# SCH_hackfest_2025-04-05_final.net
KiCad netlist of a schematic drawn in EasyEDA
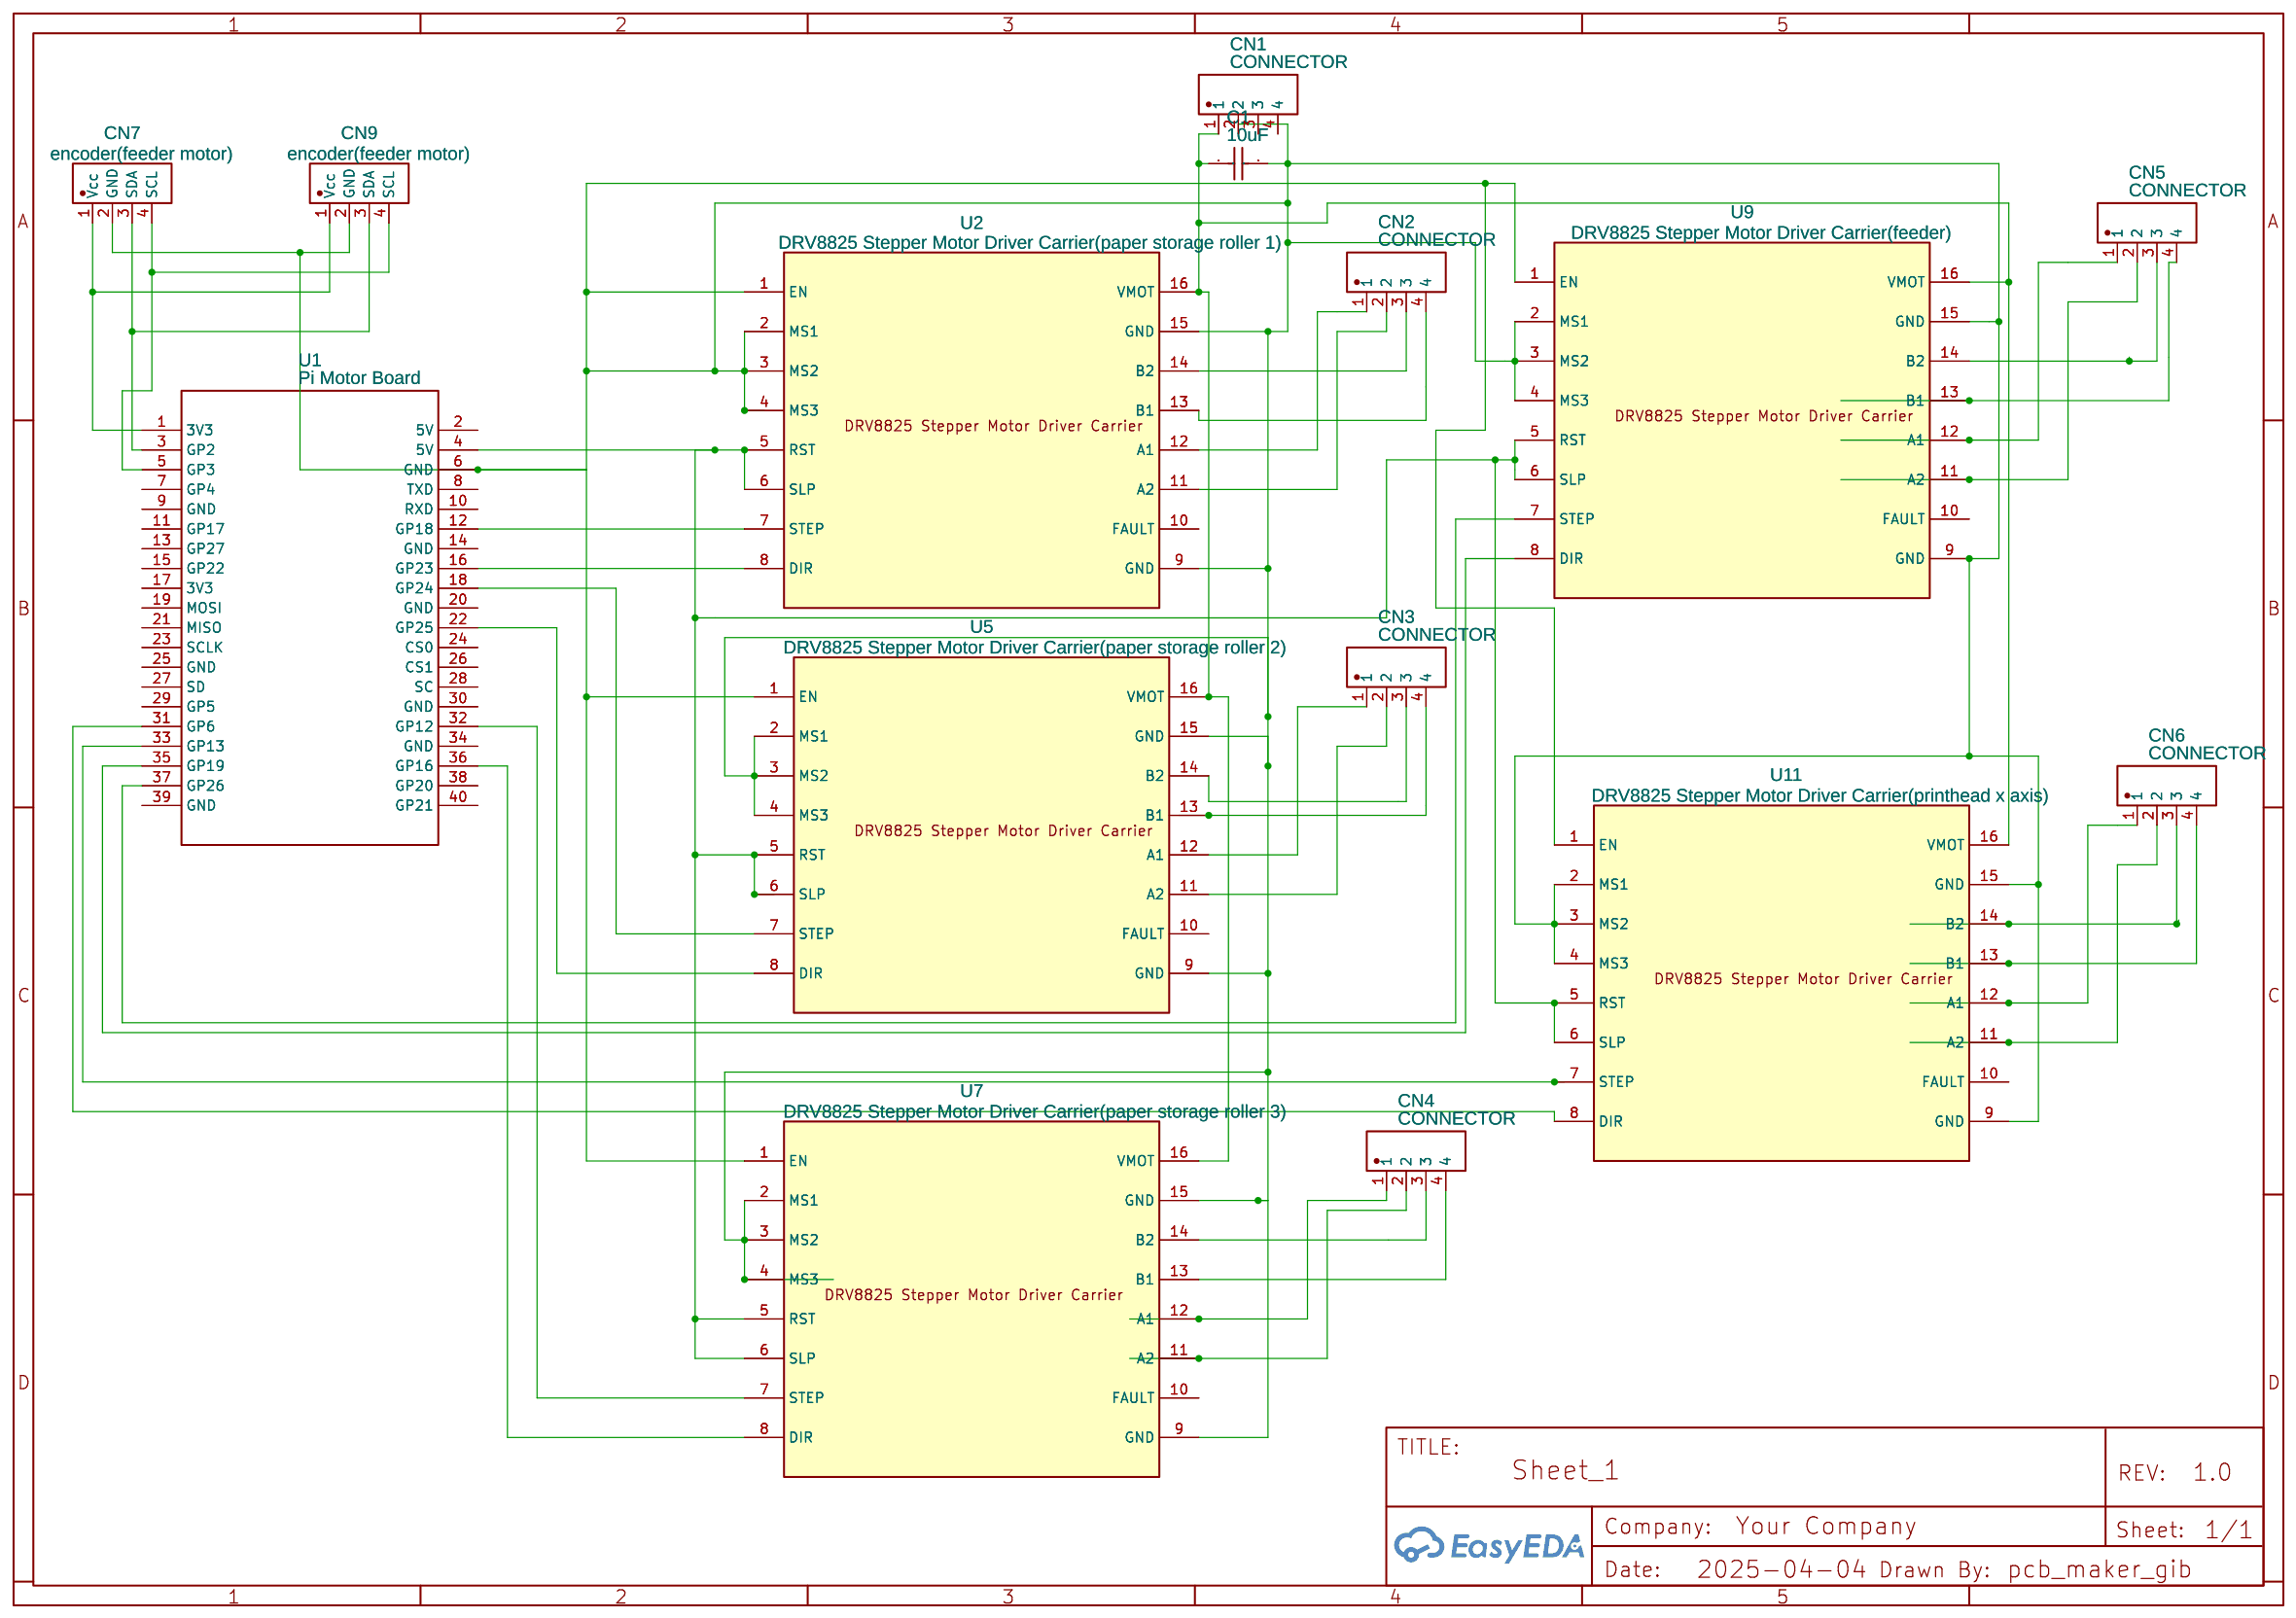
[diagram p0: schematic sheet]

(export (version "E")
  (design (tool "Eeschema 10.0.6"))
  (components
    (comp (ref "C1")
      (value "10uF")
      (fields (field (name "Manufacturer Part") "电容15nf100v"))
      (libsource (lib "") (part "CAPACITOR15NF100V"))
    )
    (comp (ref "CN1") (value "CONNECTOR") (libsource (lib "") (part "CONNECTOR_1")))
    (comp (ref "CN2") (value "CONNECTOR") (libsource (lib "") (part "CONNECTOR_1")))
    (comp (ref "CN3") (value "CONNECTOR") (libsource (lib "") (part "CONNECTOR_1")))
    (comp (ref "CN4") (value "CONNECTOR") (libsource (lib "") (part "CONNECTOR_1")))
    (comp (ref "CN5") (value "CONNECTOR") (libsource (lib "") (part "CONNECTOR_1")))
    (comp (ref "CN6") (value "CONNECTOR") (libsource (lib "") (part "CONNECTOR_1")))
    (comp (ref "CN7")
      (value "encoder(feeder motor)")
      (fields (field (name "Manufacturer Part") "CONNECTOR"))
      (libsource (lib "") (part "CONNECTOR"))
    )
    (comp (ref "CN9")
      (value "encoder(feeder motor)")
      (fields (field (name "Manufacturer Part") "CONNECTOR"))
      (libsource (lib "") (part "CONNECTOR"))
    )
    (comp (ref "U1") (value "Pi Motor Board") (libsource (lib "") (part "Pi Motor Board")))
    (comp (ref "U2")
      (value "DRV8825 Stepper Motor Driver Carrier(paper storage roller 1)")
      (libsource (lib "") (part "DRV8825 Stepper Motor Driver Carrier"))
    )
    (comp (ref "U5")
      (value "DRV8825 Stepper Motor Driver Carrier(paper storage roller 2)")
      (libsource (lib "") (part "DRV8825 Stepper Motor Driver Carrier"))
    )
    (comp (ref "U7")
      (value "DRV8825 Stepper Motor Driver Carrier(paper storage roller 3)")
      (libsource (lib "") (part "DRV8825 Stepper Motor Driver Carrier_1"))
    )
    (comp (ref "U9")
      (value "DRV8825 Stepper Motor Driver Carrier(feeder)")
      (libsource (lib "") (part "DRV8825 Stepper Motor Driver Carrier"))
    )
    (comp (ref "U11")
      (value "DRV8825 Stepper Motor Driver Carrier(printhead x axis)")
      (libsource (lib "") (part "DRV8825 Stepper Motor Driver Carrier"))
    )
  )
  (nets
    (net (code "1") (name "Net-(CN7-GND)") (class "Default")
      (node (ref "C1") (pin "2") (pinfunction "2_2") (pintype "input"))
      (node (ref "CN1") (pin "2") (pinfunction "2_2") (pintype "unspecified"))
      (node (ref "CN7") (pin "2") (pinfunction "GND_2") (pintype "unspecified"))
      (node (ref "CN9") (pin "2") (pinfunction "GND_2") (pintype "unspecified"))
      (node (ref "U1") (pin "6") (pinfunction "GND_6") (pintype "unspecified"))
      (node (ref "U11") (pin "1") (pinfunction "EN_1") (pintype "unspecified"))
      (node (ref "U11") (pin "15") (pinfunction "GND_15") (pintype "unspecified"))
      (node (ref "U11") (pin "2") (pinfunction "MS1_2") (pintype "unspecified"))
      (node (ref "U11") (pin "3") (pinfunction "MS2_3") (pintype "unspecified"))
      (node (ref "U11") (pin "4") (pinfunction "MS3_4") (pintype "unspecified"))
      (node (ref "U11") (pin "9") (pinfunction "GND_9") (pintype "unspecified"))
      (node (ref "U2") (pin "1") (pinfunction "EN_1") (pintype "unspecified"))
      (node (ref "U2") (pin "15") (pinfunction "GND_15") (pintype "unspecified"))
      (node (ref "U2") (pin "2") (pinfunction "MS1_2") (pintype "unspecified"))
      (node (ref "U2") (pin "3") (pinfunction "MS2_3") (pintype "unspecified"))
      (node (ref "U2") (pin "4") (pinfunction "MS3_4") (pintype "unspecified"))
      (node (ref "U2") (pin "9") (pinfunction "GND_9") (pintype "unspecified"))
      (node (ref "U5") (pin "1") (pinfunction "EN_1") (pintype "unspecified"))
      (node (ref "U5") (pin "15") (pinfunction "GND_15") (pintype "unspecified"))
      (node (ref "U5") (pin "2") (pinfunction "MS1_2") (pintype "unspecified"))
      (node (ref "U5") (pin "3") (pinfunction "MS2_3") (pintype "unspecified"))
      (node (ref "U5") (pin "4") (pinfunction "MS3_4") (pintype "unspecified"))
      (node (ref "U5") (pin "9") (pinfunction "GND_9") (pintype "unspecified"))
      (node (ref "U7") (pin "1") (pinfunction "EN_1") (pintype "unspecified"))
      (node (ref "U7") (pin "15") (pinfunction "GND_15") (pintype "unspecified"))
      (node (ref "U7") (pin "2") (pinfunction "MS1_2") (pintype "unspecified"))
      (node (ref "U7") (pin "3") (pinfunction "MS2_3") (pintype "unspecified"))
      (node (ref "U7") (pin "4") (pinfunction "MS3_4") (pintype "unspecified"))
      (node (ref "U7") (pin "9") (pinfunction "GND_9") (pintype "unspecified"))
      (node (ref "U9") (pin "1") (pinfunction "EN_1") (pintype "unspecified"))
      (node (ref "U9") (pin "15") (pinfunction "GND_15") (pintype "unspecified"))
      (node (ref "U9") (pin "2") (pinfunction "MS1_2") (pintype "unspecified"))
      (node (ref "U9") (pin "3") (pinfunction "MS2_3") (pintype "unspecified"))
      (node (ref "U9") (pin "4") (pinfunction "MS3_4") (pintype "unspecified"))
      (node (ref "U9") (pin "9") (pinfunction "GND_9") (pintype "unspecified"))
    )
    (net (code "2") (name "Net-(CN7-SCL)") (class "Default")
      (node (ref "CN7") (pin "4") (pinfunction "SCL_4") (pintype "unspecified"))
      (node (ref "CN9") (pin "4") (pinfunction "SCL_4") (pintype "unspecified"))
      (node (ref "U1") (pin "5") (pinfunction "GP3_5") (pintype "unspecified"))
    )
    (net (code "3") (name "Net-(CN7-SDA)") (class "Default")
      (node (ref "CN7") (pin "3") (pinfunction "SDA_3") (pintype "unspecified"))
      (node (ref "CN9") (pin "3") (pinfunction "SDA_3") (pintype "unspecified"))
      (node (ref "U1") (pin "3") (pinfunction "GP2_3") (pintype "unspecified"))
    )
    (net (code "4") (name "Net-(CN7-Vcc)") (class "Default")
      (node (ref "CN7") (pin "1") (pinfunction "Vcc_1") (pintype "unspecified"))
      (node (ref "CN9") (pin "1") (pinfunction "Vcc_1") (pintype "unspecified"))
      (node (ref "U1") (pin "1") (pinfunction "3V3_1") (pintype "unspecified"))
    )
    (net (code "5") (name "Net-(U1-GP6)") (class "Default")
      (node (ref "U1") (pin "31") (pinfunction "GP6_31") (pintype "unspecified"))
      (node (ref "U11") (pin "8") (pinfunction "DIR_8") (pintype "unspecified"))
    )
    (net (code "6") (name "Net-(U1-GP12)") (class "Default")
      (node (ref "U1") (pin "32") (pinfunction "GP12_32") (pintype "unspecified"))
      (node (ref "U7") (pin "7") (pinfunction "STEP_7") (pintype "unspecified"))
    )
    (net (code "7") (name "Net-(U1-GP13)") (class "Default")
      (node (ref "U1") (pin "33") (pinfunction "GP13_33") (pintype "unspecified"))
      (node (ref "U11") (pin "7") (pinfunction "STEP_7") (pintype "unspecified"))
    )
    (net (code "8") (name "Net-(U1-GP16)") (class "Default")
      (node (ref "U1") (pin "36") (pinfunction "GP16_36") (pintype "unspecified"))
      (node (ref "U7") (pin "8") (pinfunction "DIR_8") (pintype "unspecified"))
    )
    (net (code "9") (name "Net-(U1-GP18)") (class "Default")
      (node (ref "U1") (pin "12") (pinfunction "GP18_12") (pintype "unspecified"))
      (node (ref "U2") (pin "7") (pinfunction "STEP_7") (pintype "unspecified"))
    )
    (net (code "10") (name "Net-(U1-GP19)") (class "Default")
      (node (ref "U1") (pin "35") (pinfunction "GP19_35") (pintype "unspecified"))
      (node (ref "U9") (pin "8") (pinfunction "DIR_8") (pintype "unspecified"))
    )
    (net (code "11") (name "Net-(U1-GP23)") (class "Default")
      (node (ref "U1") (pin "16") (pinfunction "GP23_16") (pintype "unspecified"))
      (node (ref "U2") (pin "8") (pinfunction "DIR_8") (pintype "unspecified"))
    )
    (net (code "12") (name "Net-(U1-GP24)") (class "Default")
      (node (ref "U1") (pin "18") (pinfunction "GP24_18") (pintype "unspecified"))
      (node (ref "U5") (pin "7") (pinfunction "STEP_7") (pintype "unspecified"))
    )
    (net (code "13") (name "Net-(U1-GP25)") (class "Default")
      (node (ref "U1") (pin "22") (pinfunction "GP25_22") (pintype "unspecified"))
      (node (ref "U5") (pin "8") (pinfunction "DIR_8") (pintype "unspecified"))
    )
    (net (code "14") (name "Net-(U1-GP26)") (class "Default")
      (node (ref "U1") (pin "37") (pinfunction "GP26_37") (pintype "unspecified"))
      (node (ref "U9") (pin "7") (pinfunction "STEP_7") (pintype "unspecified"))
    )
    (net (code "15") (name "Net-(U2-A1)") (class "Default")
      (node (ref "CN2") (pin "1") (pinfunction "1_1") (pintype "unspecified"))
      (node (ref "U2") (pin "12") (pinfunction "A1_12") (pintype "unspecified"))
    )
    (net (code "16") (name "Net-(U2-A2)") (class "Default")
      (node (ref "CN2") (pin "2") (pinfunction "2_2") (pintype "unspecified"))
      (node (ref "U2") (pin "11") (pinfunction "A2_11") (pintype "unspecified"))
    )
    (net (code "17") (name "Net-(U2-B1)") (class "Default")
      (node (ref "CN2") (pin "4") (pinfunction "4_4") (pintype "unspecified"))
      (node (ref "U2") (pin "13") (pinfunction "B1_13") (pintype "unspecified"))
    )
    (net (code "18") (name "Net-(U2-B2)") (class "Default")
      (node (ref "CN2") (pin "3") (pinfunction "3_3") (pintype "unspecified"))
      (node (ref "U2") (pin "14") (pinfunction "B2_14") (pintype "unspecified"))
    )
    (net (code "19") (name "Net-(U5-A1)") (class "Default")
      (node (ref "CN3") (pin "1") (pinfunction "1_1") (pintype "unspecified"))
      (node (ref "U5") (pin "12") (pinfunction "A1_12") (pintype "unspecified"))
    )
    (net (code "20") (name "Net-(U5-A2)") (class "Default")
      (node (ref "CN3") (pin "2") (pinfunction "2_2") (pintype "unspecified"))
      (node (ref "U5") (pin "11") (pinfunction "A2_11") (pintype "unspecified"))
    )
    (net (code "21") (name "Net-(U5-B1)") (class "Default")
      (node (ref "CN3") (pin "4") (pinfunction "4_4") (pintype "unspecified"))
      (node (ref "U5") (pin "13") (pinfunction "B1_13") (pintype "unspecified"))
    )
    (net (code "22") (name "Net-(U5-B2)") (class "Default")
      (node (ref "CN3") (pin "3") (pinfunction "3_3") (pintype "unspecified"))
      (node (ref "U5") (pin "14") (pinfunction "B2_14") (pintype "unspecified"))
    )
    (net (code "23") (name "Net-(U7-A1)") (class "Default")
      (node (ref "CN4") (pin "1") (pinfunction "1_1") (pintype "unspecified"))
      (node (ref "U7") (pin "12") (pinfunction "A1_12") (pintype "unspecified"))
    )
    (net (code "24") (name "Net-(U7-A2)") (class "Default")
      (node (ref "CN4") (pin "2") (pinfunction "2_2") (pintype "unspecified"))
      (node (ref "U7") (pin "11") (pinfunction "A2_11") (pintype "unspecified"))
    )
    (net (code "25") (name "Net-(U7-B1)") (class "Default")
      (node (ref "CN4") (pin "4") (pinfunction "4_4") (pintype "unspecified"))
      (node (ref "U7") (pin "13") (pinfunction "B1_13") (pintype "unspecified"))
    )
    (net (code "26") (name "Net-(U7-B2)") (class "Default")
      (node (ref "CN4") (pin "3") (pinfunction "3_3") (pintype "unspecified"))
      (node (ref "U7") (pin "14") (pinfunction "B2_14") (pintype "unspecified"))
    )
    (net (code "27") (name "Net-(U9-A1)") (class "Default")
      (node (ref "CN5") (pin "1") (pinfunction "1_1") (pintype "unspecified"))
      (node (ref "U9") (pin "12") (pinfunction "A1_12") (pintype "unspecified"))
    )
    (net (code "28") (name "Net-(U9-A2)") (class "Default")
      (node (ref "CN5") (pin "2") (pinfunction "2_2") (pintype "unspecified"))
      (node (ref "U9") (pin "11") (pinfunction "A2_11") (pintype "unspecified"))
    )
    (net (code "29") (name "Net-(U9-B1)") (class "Default")
      (node (ref "CN5") (pin "4") (pinfunction "4_4") (pintype "unspecified"))
      (node (ref "U9") (pin "13") (pinfunction "B1_13") (pintype "unspecified"))
    )
    (net (code "30") (name "Net-(U9-B2)") (class "Default")
      (node (ref "CN5") (pin "3") (pinfunction "3_3") (pintype "unspecified"))
      (node (ref "U9") (pin "14") (pinfunction "B2_14") (pintype "unspecified"))
    )
    (net (code "31") (name "Net-(U11-A1)") (class "Default")
      (node (ref "CN6") (pin "1") (pinfunction "1_1") (pintype "unspecified"))
      (node (ref "U11") (pin "12") (pinfunction "A1_12") (pintype "unspecified"))
    )
    (net (code "32") (name "Net-(U11-A2)") (class "Default")
      (node (ref "CN6") (pin "2") (pinfunction "2_2") (pintype "unspecified"))
      (node (ref "U11") (pin "11") (pinfunction "A2_11") (pintype "unspecified"))
    )
    (net (code "33") (name "Net-(U11-B1)") (class "Default")
      (node (ref "CN6") (pin "4") (pinfunction "4_4") (pintype "unspecified"))
      (node (ref "U11") (pin "13") (pinfunction "B1_13") (pintype "unspecified"))
    )
    (net (code "34") (name "Net-(U11-B2)") (class "Default")
      (node (ref "CN6") (pin "3") (pinfunction "3_3") (pintype "unspecified"))
      (node (ref "U11") (pin "14") (pinfunction "B2_14") (pintype "unspecified"))
    )
    (net (code "35") (name "Net-(U11-RST)") (class "Default")
      (node (ref "U1") (pin "4") (pinfunction "5V_4") (pintype "unspecified"))
      (node (ref "U11") (pin "5") (pinfunction "RST_5") (pintype "unspecified"))
      (node (ref "U11") (pin "6") (pinfunction "SLP_6") (pintype "unspecified"))
      (node (ref "U2") (pin "5") (pinfunction "RST_5") (pintype "unspecified"))
      (node (ref "U2") (pin "6") (pinfunction "SLP_6") (pintype "unspecified"))
      (node (ref "U5") (pin "5") (pinfunction "RST_5") (pintype "unspecified"))
      (node (ref "U5") (pin "6") (pinfunction "SLP_6") (pintype "unspecified"))
      (node (ref "U7") (pin "5") (pinfunction "RST_5") (pintype "unspecified"))
      (node (ref "U7") (pin "6") (pinfunction "SLP_6") (pintype "unspecified"))
      (node (ref "U9") (pin "5") (pinfunction "RST_5") (pintype "unspecified"))
      (node (ref "U9") (pin "6") (pinfunction "SLP_6") (pintype "unspecified"))
    )
    (net (code "36") (name "Net-(U11-VMOT)") (class "Default")
      (node (ref "C1") (pin "1") (pinfunction "1_1") (pintype "input"))
      (node (ref "CN1") (pin "1") (pinfunction "1_1") (pintype "unspecified"))
      (node (ref "U11") (pin "16") (pinfunction "VMOT_16") (pintype "unspecified"))
      (node (ref "U2") (pin "16") (pinfunction "VMOT_16") (pintype "unspecified"))
      (node (ref "U5") (pin "16") (pinfunction "VMOT_16") (pintype "unspecified"))
      (node (ref "U7") (pin "16") (pinfunction "VMOT_16") (pintype "unspecified"))
      (node (ref "U9") (pin "16") (pinfunction "VMOT_16") (pintype "unspecified"))
    )
    (net (code "37") (name "unconnected-(CN1-Pad3)") (class "Default")
      (node (ref "CN1") (pin "3") (pinfunction "3_3") (pintype "unspecified"))
    )
    (net (code "38") (name "unconnected-(CN1-Pad4)") (class "Default")
      (node (ref "CN1") (pin "4") (pinfunction "4_4") (pintype "unspecified"))
    )
    (net (code "39") (name "unconnected-(U1-3V3-Pad17)") (class "Default")
      (node (ref "U1") (pin "17") (pinfunction "3V3_17") (pintype "unspecified"))
    )
    (net (code "40") (name "unconnected-(U1-5V-Pad2)") (class "Default")
      (node (ref "U1") (pin "2") (pinfunction "5V_2") (pintype "unspecified"))
    )
    (net (code "41") (name "unconnected-(U1-CS0-Pad24)") (class "Default")
      (node (ref "U1") (pin "24") (pinfunction "CS0_24") (pintype "unspecified"))
    )
    (net (code "42") (name "unconnected-(U1-CS1-Pad26)") (class "Default")
      (node (ref "U1") (pin "26") (pinfunction "CS1_26") (pintype "unspecified"))
    )
    (net (code "43") (name "unconnected-(U1-GND-Pad9)") (class "Default")
      (node (ref "U1") (pin "9") (pinfunction "GND_9") (pintype "unspecified"))
    )
    (net (code "44") (name "unconnected-(U1-GND-Pad14)") (class "Default")
      (node (ref "U1") (pin "14") (pinfunction "GND_14") (pintype "unspecified"))
    )
    (net (code "45") (name "unconnected-(U1-GND-Pad20)") (class "Default")
      (node (ref "U1") (pin "20") (pinfunction "GND_20") (pintype "unspecified"))
    )
    (net (code "46") (name "unconnected-(U1-GND-Pad25)") (class "Default")
      (node (ref "U1") (pin "25") (pinfunction "GND_25") (pintype "unspecified"))
    )
    (net (code "47") (name "unconnected-(U1-GND-Pad30)") (class "Default")
      (node (ref "U1") (pin "30") (pinfunction "GND_30") (pintype "unspecified"))
    )
    (net (code "48") (name "unconnected-(U1-GND-Pad34)") (class "Default")
      (node (ref "U1") (pin "34") (pinfunction "GND_34") (pintype "unspecified"))
    )
    (net (code "49") (name "unconnected-(U1-GND-Pad39)") (class "Default")
      (node (ref "U1") (pin "39") (pinfunction "GND_39") (pintype "unspecified"))
    )
    (net (code "50") (name "unconnected-(U1-GP4-Pad7)") (class "Default")
      (node (ref "U1") (pin "7") (pinfunction "GP4_7") (pintype "unspecified"))
    )
    (net (code "51") (name "unconnected-(U1-GP5-Pad29)") (class "Default")
      (node (ref "U1") (pin "29") (pinfunction "GP5_29") (pintype "unspecified"))
    )
    (net (code "52") (name "unconnected-(U1-GP17-Pad11)") (class "Default")
      (node (ref "U1") (pin "11") (pinfunction "GP17_11") (pintype "unspecified"))
    )
    (net (code "53") (name "unconnected-(U1-GP20-Pad38)") (class "Default")
      (node (ref "U1") (pin "38") (pinfunction "GP20_38") (pintype "unspecified"))
    )
    (net (code "54") (name "unconnected-(U1-GP21-Pad40)") (class "Default")
      (node (ref "U1") (pin "40") (pinfunction "GP21_40") (pintype "unspecified"))
    )
    (net (code "55") (name "unconnected-(U1-GP22-Pad15)") (class "Default")
      (node (ref "U1") (pin "15") (pinfunction "GP22_15") (pintype "unspecified"))
    )
    (net (code "56") (name "unconnected-(U1-GP27-Pad13)") (class "Default")
      (node (ref "U1") (pin "13") (pinfunction "GP27_13") (pintype "unspecified"))
    )
    (net (code "57") (name "unconnected-(U1-MISO-Pad21)") (class "Default")
      (node (ref "U1") (pin "21") (pinfunction "MISO_21") (pintype "unspecified"))
    )
    (net (code "58") (name "unconnected-(U1-MOSI-Pad19)") (class "Default")
      (node (ref "U1") (pin "19") (pinfunction "MOSI_19") (pintype "unspecified"))
    )
    (net (code "59") (name "unconnected-(U1-RXD-Pad10)") (class "Default")
      (node (ref "U1") (pin "10") (pinfunction "RXD_10") (pintype "unspecified"))
    )
    (net (code "60") (name "unconnected-(U1-SC-Pad28)") (class "Default")
      (node (ref "U1") (pin "28") (pinfunction "SC_28") (pintype "unspecified"))
    )
    (net (code "61") (name "unconnected-(U1-SCLK-Pad23)") (class "Default")
      (node (ref "U1") (pin "23") (pinfunction "SCLK_23") (pintype "unspecified"))
    )
    (net (code "62") (name "unconnected-(U1-SD-Pad27)") (class "Default")
      (node (ref "U1") (pin "27") (pinfunction "SD_27") (pintype "unspecified"))
    )
    (net (code "63") (name "unconnected-(U1-TXD-Pad8)") (class "Default")
      (node (ref "U1") (pin "8") (pinfunction "TXD_8") (pintype "unspecified"))
    )
    (net (code "64") (name "unconnected-(U2-FAULT-Pad10)") (class "Default")
      (node (ref "U2") (pin "10") (pinfunction "FAULT_10") (pintype "unspecified"))
    )
    (net (code "65") (name "unconnected-(U5-FAULT-Pad10)") (class "Default")
      (node (ref "U5") (pin "10") (pinfunction "FAULT_10") (pintype "unspecified"))
    )
    (net (code "66") (name "unconnected-(U7-FAULT-Pad10)") (class "Default")
      (node (ref "U7") (pin "10") (pinfunction "FAULT_10") (pintype "unspecified"))
    )
    (net (code "67") (name "unconnected-(U9-FAULT-Pad10)") (class "Default")
      (node (ref "U9") (pin "10") (pinfunction "FAULT_10") (pintype "unspecified"))
    )
    (net (code "68") (name "unconnected-(U11-FAULT-Pad10)") (class "Default")
      (node (ref "U11") (pin "10") (pinfunction "FAULT_10") (pintype "unspecified"))
    )
  )
)
